# Kasli-DIOT.net
KiCad netlist of a schematic drawn in Altium Designer
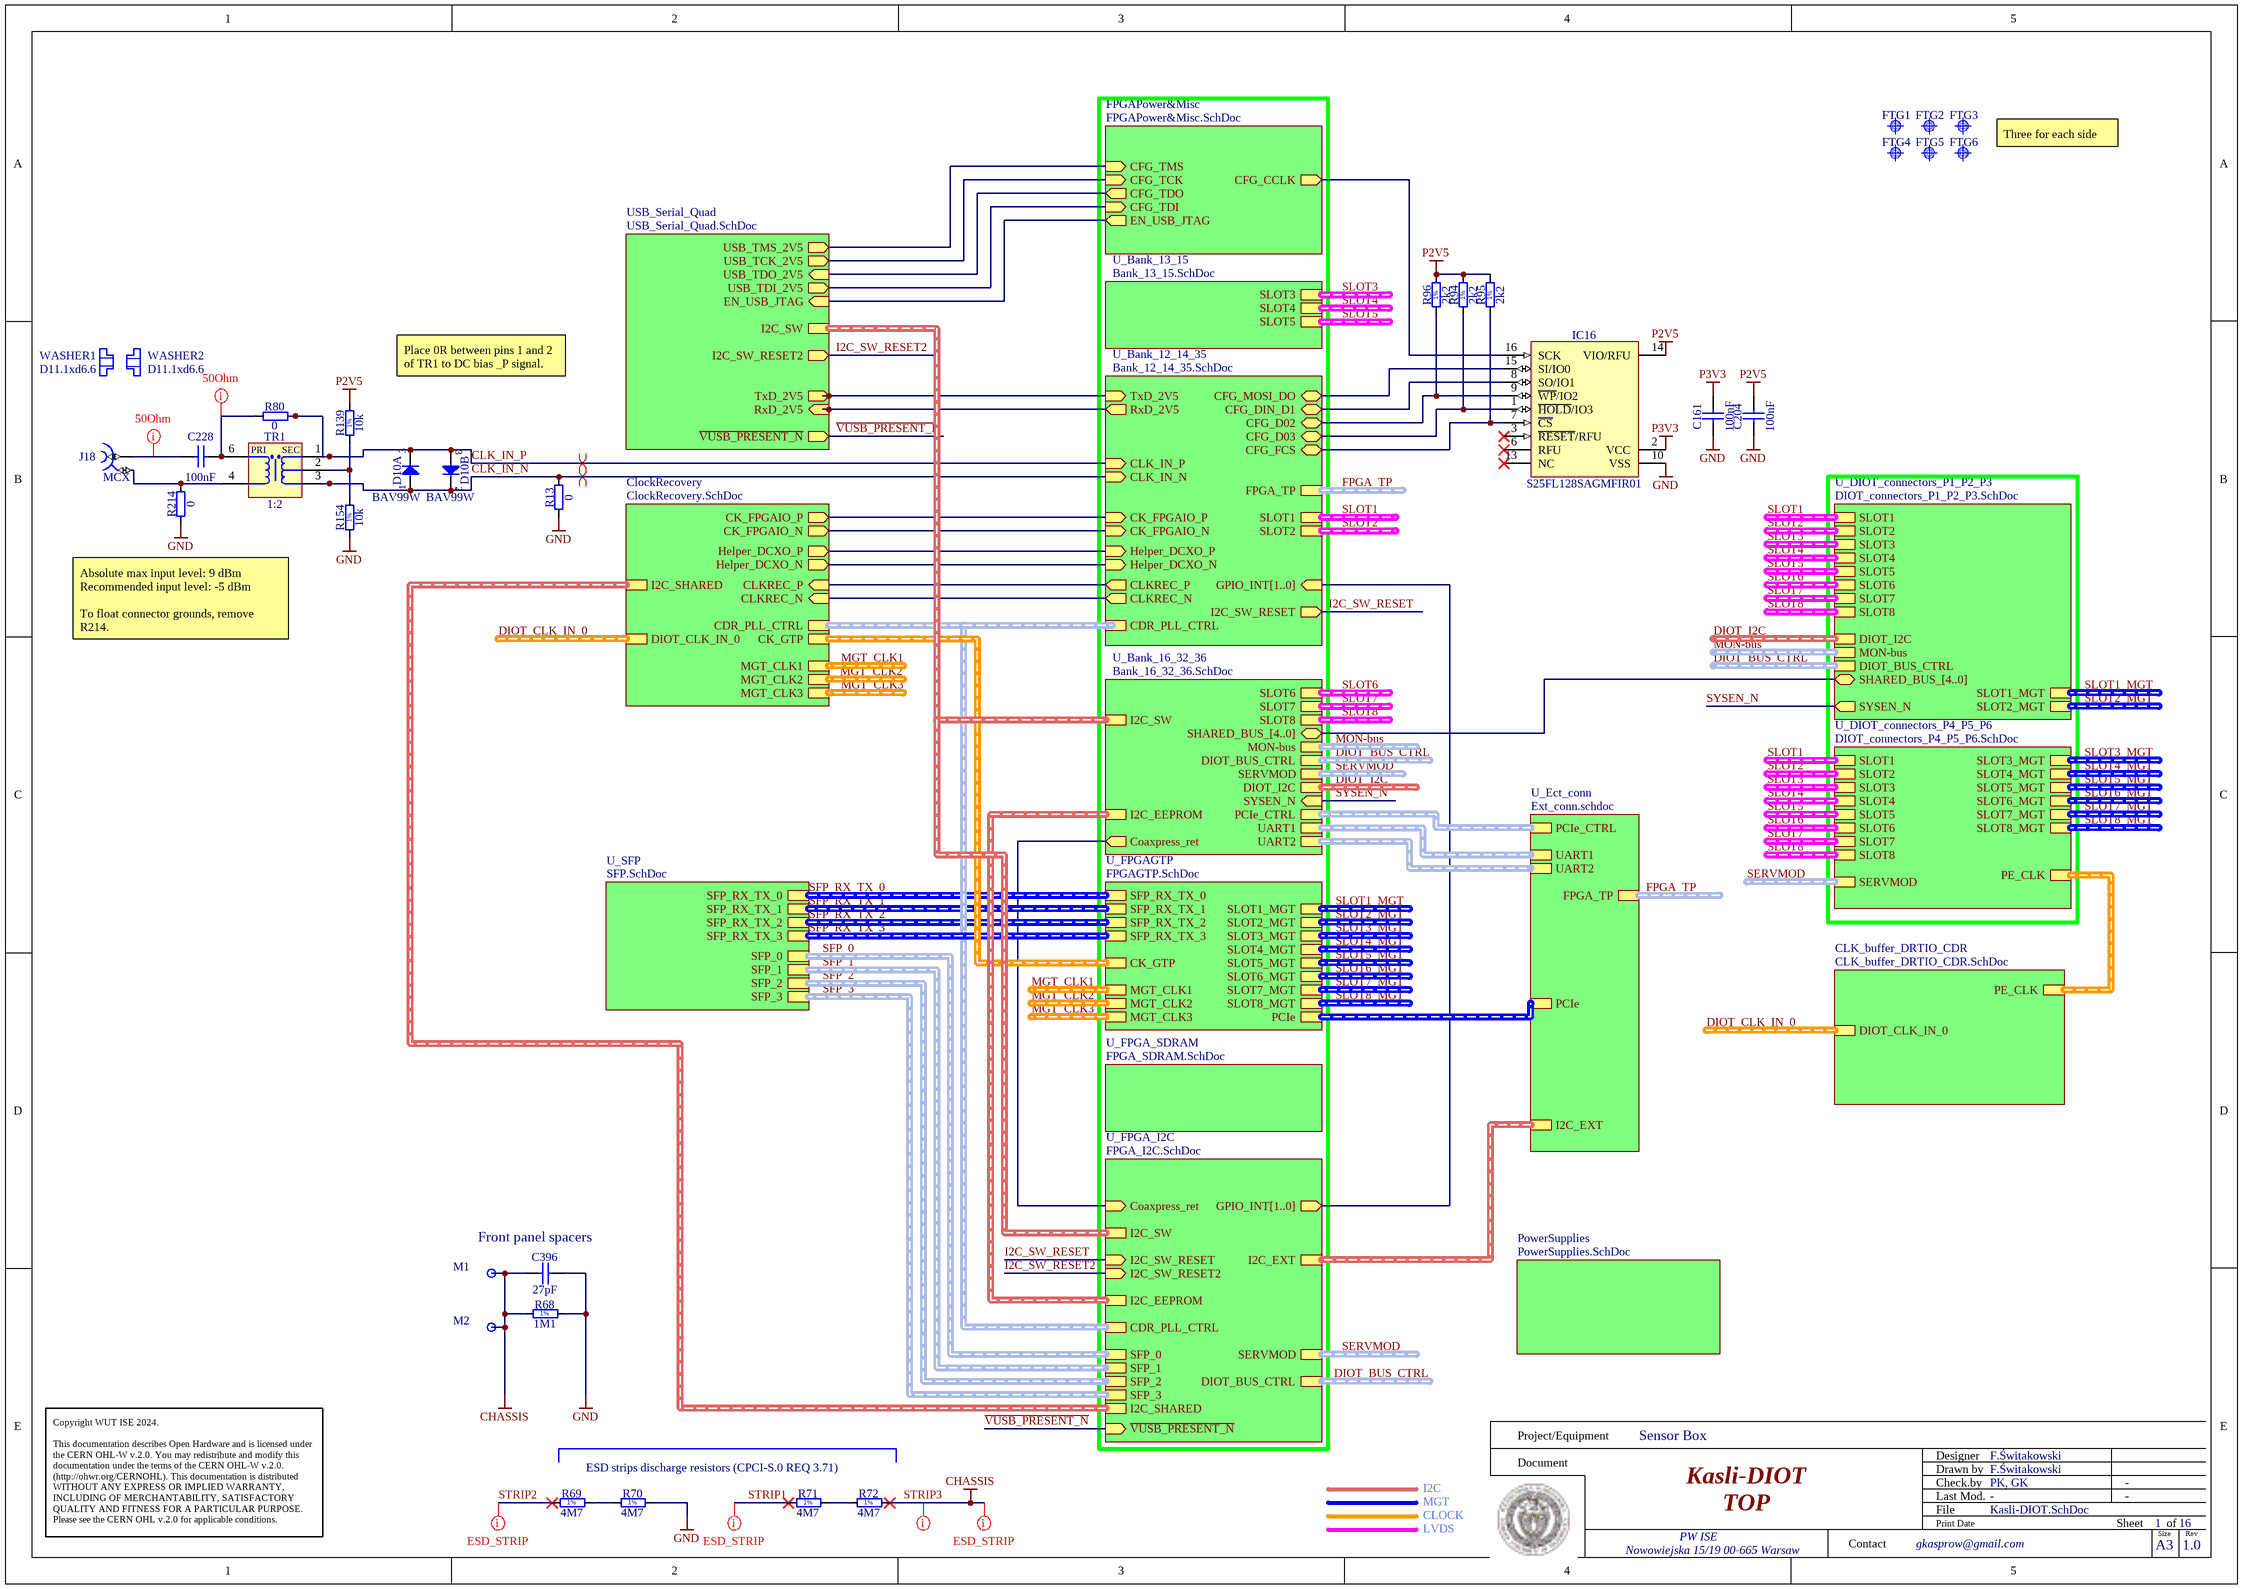
[diagram p0: Kasli-DIOT.SchDoc]

(export (version "E")
  (design (tool "Eeschema 10.0.6"))
  (components
    (comp (ref "C161")
      (value "100nF")
      (footprint "CAPC1005X55N")
      (description "Non-polarised capacitor")
      (fields
        (field (name "PART NUMBER") "CC0402_100NF_16V_10%_X7R")
        (field (name "VOLTAGE") "16V")
        (field (name "AUTHOR") "CERN DEM JLC")
      )
      (libsource (lib "Capacitors") (part "Capacitor - non polarized"))
    )
    (comp (ref "C204")
      (value "100nF")
      (footprint "CAPC1005X55N")
      (description "Non-polarised capacitor")
      (fields
        (field (name "PART NUMBER") "CC0402_100NF_16V_10%_X7R")
        (field (name "VOLTAGE") "16V")
        (field (name "AUTHOR") "CERN DEM JLC")
      )
      (libsource (lib "Capacitors") (part "Capacitor - non polarized"))
    )
    (comp (ref "C228")
      (value "100nF")
      (footprint "CAPC0603X33N")
      (description "Non-polarised capacitor")
      (fields
        (field (name "PART NUMBER") "CC0201_100NF_6.3V_10%_X5R")
        (field (name "VOLTAGE") "6.3V")
        (field (name "AUTHOR") "CERN DEM JLC")
      )
      (libsource (lib "Capacitors") (part "Capacitor - non polarized"))
    )
    (comp (ref "C396")
      (value "27pF")
      (footprint "CAPC1005X55N")
      (description "Non-polarised capacitor")
      (fields
        (field (name "PART NUMBER") "CC0402_27PF_50V_5%_C0G")
        (field (name "VOLTAGE") "50V")
        (field (name "AUTHOR") "CERN DEM JLC")
      )
      (libsource (lib "Capacitors") (part "Capacitor - non polarized"))
    )
    (comp (ref "D10")
      (value "BAV99W")
      (footprint "SOT65P210X110-3N")
      (description "Serial Diode")
      (fields
        (field (name "PART NUMBER") "BAV99W-7-F")
        (field (name "VOLTAGE") "75V")
        (field (name "AUTHOR") "CERN DEM MR")
      )
      (libsource (lib "ICs And Semiconductors") (part "Diode x2 A1C3_A3C2"))
    )
    (comp (ref "FTG1")
      (value "Use only in PCB")
      (footprint "FIDUCIAL_TOP_S100-200")
      (description "Fiducial Target")
      (fields (field (name "PART NUMBER") "FIDUCIAL_TARGET_S100-200") (field (name "AUTHOR") "CERN DEM JLC"))
      (libsource (lib "Eletro-mechanical") (part "Fiducial Target"))
    )
    (comp (ref "FTG2")
      (value "Use only in PCB")
      (footprint "FIDUCIAL_TOP_S100-200")
      (description "Fiducial Target")
      (fields (field (name "PART NUMBER") "FIDUCIAL_TARGET_S100-200") (field (name "AUTHOR") "CERN DEM JLC"))
      (libsource (lib "Eletro-mechanical") (part "Fiducial Target"))
    )
    (comp (ref "FTG3")
      (value "Use only in PCB")
      (footprint "FIDUCIAL_TOP_S100-200")
      (description "Fiducial Target")
      (fields (field (name "PART NUMBER") "FIDUCIAL_TARGET_S100-200") (field (name "AUTHOR") "CERN DEM JLC"))
      (libsource (lib "Eletro-mechanical") (part "Fiducial Target"))
    )
    (comp (ref "FTG4")
      (value "Use only in PCB")
      (footprint "FIDUCIAL_TOP_S100-200")
      (description "Fiducial Target")
      (fields (field (name "PART NUMBER") "FIDUCIAL_TARGET_S100-200") (field (name "AUTHOR") "CERN DEM JLC"))
      (libsource (lib "Eletro-mechanical") (part "Fiducial Target"))
    )
    (comp (ref "FTG5")
      (value "Use only in PCB")
      (footprint "FIDUCIAL_TOP_S100-200")
      (description "Fiducial Target")
      (fields (field (name "PART NUMBER") "FIDUCIAL_TARGET_S100-200") (field (name "AUTHOR") "CERN DEM JLC"))
      (libsource (lib "Eletro-mechanical") (part "Fiducial Target"))
    )
    (comp (ref "FTG6")
      (value "Use only in PCB")
      (footprint "FIDUCIAL_TOP_S100-200")
      (description "Fiducial Target")
      (fields (field (name "PART NUMBER") "FIDUCIAL_TARGET_S100-200") (field (name "AUTHOR") "CERN DEM JLC"))
      (libsource (lib "Eletro-mechanical") (part "Fiducial Target"))
    )
    (comp (ref "IC16")
      (value "S25FL128SAGMFIR01")
      (footprint "SOIC127P1030X265-16N")
      (fields (field (name "MANUFACTURER") "SPANSION") (field (name "AUTHOR") "CERN DEM JLC"))
      (libsource (lib "ICs And Semiconductors") (part "S25FL128SAGMFIR01"))
    )
    (comp (ref "J18")
      (value "MCX")
      (footprint "AMPHENOL_919-383J-51A")
      (fields
        (field (name "PART NUMBER") "AMPHENOL_919-383J-51A")
        (field (name "MANUFACTURER") "AMPHENOL")
        (field (name "MANUFACTURER PART NUMBER") "919-383J-51A")
        (field (name "AUTHOR") "CERN DEM BC")
      )
      (libsource (lib "Connectors") (part "Coax_1Female_1Shield"))
    )
    (comp (ref "M1")
      (value "Plated Hole")
      (footprint "MTG300_600")
      (description "Single Terminal Socket")
      (fields (field (name "PART NUMBER") "PLATED_HOLE3.0_PAD6.0") (field (name "AUTHOR") "CERN DEM JLC"))
      (libsource (lib "Eletro-mechanical") (part "Single Terminal Socket"))
    )
    (comp (ref "M2")
      (value "Plated Hole")
      (footprint "MTG300_600")
      (description "Single Terminal Socket")
      (fields (field (name "PART NUMBER") "PLATED_HOLE3.0_PAD6.0") (field (name "AUTHOR") "CERN DEM JLC"))
      (libsource (lib "Eletro-mechanical") (part "Single Terminal Socket"))
    )
    (comp (ref "R13")
      (value "0")
      (footprint "RESC1005X40N")
      (description "Resistor")
      (fields
        (field (name "PART NUMBER") "R0402_0R_JUMPER")
        (field (name "MANUFACTURER") "GENERIC")
        (field (name "AUTHOR") "CERN DEM JLC")
      )
      (libsource (lib "Resistors") (part "Resistor"))
    )
    (comp (ref "R68")
      (value "1M1")
      (footprint "RESC2012X60N")
      (description "Resistor - 1%")
      (fields
        (field (name "PART NUMBER") "R0805_1M1_1%_0.125W_100PPM")
        (field (name "POWER") "0.125W")
        (field (name "AUTHOR") "CERN DEM JLC")
      )
      (libsource (lib "Resistors") (part "Resistor - 1%"))
    )
    (comp (ref "R69")
      (value "4M7")
      (footprint "RESC2113X55N")
      (description "Resistor - 1%")
      (fields
        (field (name "PART NUMBER") "R0805_4M7_1%_0.125W_100PPM_VISHAY_CRCW e3")
        (field (name "POWER") "0.125W")
        (field (name "AUTHOR") "CERN DEM BR")
      )
      (libsource (lib "Resistors") (part "Resistor - 1%"))
    )
    (comp (ref "R70")
      (value "4M7")
      (footprint "RESC2113X55N")
      (description "Resistor - 1%")
      (fields
        (field (name "PART NUMBER") "R0805_4M7_1%_0.125W_100PPM_VISHAY_CRCW e3")
        (field (name "POWER") "0.125W")
        (field (name "AUTHOR") "CERN DEM BR")
      )
      (libsource (lib "Resistors") (part "Resistor - 1%"))
    )
    (comp (ref "R71")
      (value "4M7")
      (footprint "RESC2113X55N")
      (description "Resistor - 1%")
      (fields
        (field (name "PART NUMBER") "R0805_4M7_1%_0.125W_100PPM_VISHAY_CRCW e3")
        (field (name "POWER") "0.125W")
        (field (name "AUTHOR") "CERN DEM BR")
      )
      (libsource (lib "Resistors") (part "Resistor - 1%"))
    )
    (comp (ref "R72")
      (value "4M7")
      (footprint "RESC2113X55N")
      (description "Resistor - 1%")
      (fields
        (field (name "PART NUMBER") "R0805_4M7_1%_0.125W_100PPM_VISHAY_CRCW e3")
        (field (name "POWER") "0.125W")
        (field (name "AUTHOR") "CERN DEM BR")
      )
      (libsource (lib "Resistors") (part "Resistor - 1%"))
    )
    (comp (ref "R80")
      (value "0")
      (footprint "RESC1005X40N")
      (description "Resistor")
      (fields
        (field (name "PART NUMBER") "R0402_0R_JUMPER")
        (field (name "MANUFACTURER") "GENERIC")
        (field (name "AUTHOR") "CERN DEM JLC")
      )
      (libsource (lib "Resistors") (part "Resistor"))
    )
    (comp (ref "R94")
      (value "2k2")
      (footprint "RESC1005X40N")
      (description "Resistor - 1%")
      (fields
        (field (name "PART NUMBER") "R0402_2K2_1%_0.0625W_100PPM")
        (field (name "POWER") "0.0625W")
        (field (name "AUTHOR") "CERN DEM JLC")
      )
      (libsource (lib "Resistors") (part "Resistor - 1%"))
    )
    (comp (ref "R95")
      (value "2k2")
      (footprint "RESC1005X40N")
      (description "Resistor - 1%")
      (fields
        (field (name "PART NUMBER") "R0402_2K2_1%_0.0625W_100PPM")
        (field (name "POWER") "0.0625W")
        (field (name "AUTHOR") "CERN DEM JLC")
      )
      (libsource (lib "Resistors") (part "Resistor - 1%"))
    )
    (comp (ref "R96")
      (value "2k2")
      (footprint "RESC1005X40N")
      (description "Resistor - 1%")
      (fields
        (field (name "PART NUMBER") "R0402_2K2_1%_0.0625W_100PPM")
        (field (name "POWER") "0.0625W")
        (field (name "AUTHOR") "CERN DEM JLC")
      )
      (libsource (lib "Resistors") (part "Resistor - 1%"))
    )
    (comp (ref "R139")
      (value "10k")
      (footprint "RESC1005X40N")
      (description "Resistor - 1%")
      (fields
        (field (name "PART NUMBER") "R0402_10K_1%_0.0625W_100PPM")
        (field (name "POWER") "0.0625W")
        (field (name "AUTHOR") "CERN DEM JLC")
      )
      (libsource (lib "Resistors") (part "Resistor - 1%"))
    )
    (comp (ref "R154")
      (value "10k")
      (footprint "RESC1005X40N")
      (description "Resistor - 1%")
      (fields
        (field (name "PART NUMBER") "R0402_10K_1%_0.0625W_100PPM")
        (field (name "POWER") "0.0625W")
        (field (name "AUTHOR") "CERN DEM JLC")
      )
      (libsource (lib "Resistors") (part "Resistor - 1%"))
    )
    (comp (ref "R214")
      (value "0")
      (footprint "RESC1005X40N")
      (description "Resistor")
      (fields
        (field (name "PART NUMBER") "R0402_0R_JUMPER")
        (field (name "MANUFACTURER") "GENERIC")
        (field (name "AUTHOR") "CERN DEM JLC")
      )
      (libsource (lib "Resistors") (part "Resistor"))
    )
    (comp (ref "TR1")
      (value "1:2")
      (footprint "XFMR_MINI-CIRCUITS_AT1521")
      (description "50 Ohms 3 to 300MHz RF Transformer")
      (fields
        (field (name "PART NUMBER") "XFMR_MINI-CIRCUITS_TC2-1TX+")
        (field (name "MANUFACTURER") "MINI-CIRCUITS")
        (field (name "AUTHOR") "CERN DEM MR")
      )
      (libsource (lib "Inductors & Transformers") (part "XFMR_MINI-CIRCUITS_TC2-1TX+"))
    )
    (comp (ref "WASHER1")
      (value "D11.1xd6.6")
      (footprint "Keystone_7687")
      (description "SMA_Shoulder Washer")
      (fields
        (field (name "PART NUMBER") "Keystone 7687")
        (field (name "MANUFACTURER") "Keystone")
        (field (name "AUTHOR") "GK")
      )
      (libsource (lib "LIBRARY_SCH") (part "Keystone_7687"))
    )
    (comp (ref "WASHER2")
      (value "D11.1xd6.6")
      (footprint "Keystone_7687")
      (description "SMA_Shoulder Washer")
      (fields
        (field (name "PART NUMBER") "Keystone 7687")
        (field (name "MANUFACTURER") "Keystone")
        (field (name "AUTHOR") "GK")
      )
      (libsource (lib "LIBRARY_SCH") (part "Keystone_7687"))
    )
  )
  (nets
    (net (code "35") (name "/CFG_CCLK") (class "Default")
      (node (ref "IC16") (pin "16") (pinfunction "SCK_16") (pintype "input"))
    )
    (net (code "36") (name "/CFG_D02") (class "Default")
      (node (ref "IC16") (pin "9") (pinfunction "~{WP}/IO2_9") (pintype "bidirectional"))
      (node (ref "R96") (pin "1") (pinfunction "1_1") (pintype "passive"))
    )
    (net (code "37") (name "/CFG_D03") (class "Default")
      (node (ref "IC16") (pin "1") (pinfunction "~{HOLD}/IO3_1") (pintype "bidirectional"))
      (node (ref "R94") (pin "1") (pinfunction "1_1") (pintype "passive"))
    )
    (net (code "38") (name "/CFG_DIN_D1") (class "Default")
      (node (ref "IC16") (pin "8") (pinfunction "SO/IO1_8") (pintype "bidirectional"))
    )
    (net (code "39") (name "/CFG_FCS") (class "Default")
      (node (ref "IC16") (pin "7") (pinfunction "~{CS}_7") (pintype "input"))
      (node (ref "R95") (pin "1") (pinfunction "1_1") (pintype "passive"))
    )
    (net (code "40") (name "/CFG_MOSI_DO") (class "Default")
      (node (ref "IC16") (pin "15") (pinfunction "SI/IO0_15") (pintype "bidirectional"))
    )
    (net (code "47") (name "/CLK_IN_N") (class "Default")
      (node (ref "D10") (pin "1") (pinfunction "A_1") (pintype "passive"))
      (node (ref "D10") (pin "2") (pinfunction "C_2") (pintype "passive"))
      (node (ref "R13") (pin "2") (pinfunction "2_2") (pintype "passive"))
      (node (ref "TR1") (pin "3") (pinfunction "S_3") (pintype "passive"))
    )
    (net (code "48") (name "/CLK_IN_P") (class "Default")
      (node (ref "D10") (pin "3") (pinfunction "COMAC_3") (pintype "passive"))
      (node (ref "R80") (pin "2") (pinfunction "2_2") (pintype "passive"))
      (node (ref "TR1") (pin "1") (pinfunction "SDOT_1") (pintype "passive"))
    )
    (net (code "65") (name "/STRIP1") (class "Default")
      (node (ref "R71") (pin "1") (pinfunction "1_1") (pintype "passive+no_connect"))
    )
    (net (code "66") (name "/STRIP2") (class "Default")
      (node (ref "R69") (pin "1") (pinfunction "1_1") (pintype "passive+no_connect"))
    )
    (net (code "108") (name "CHASSIS") (class "Default")
      (node (ref "C396") (pin "1") (pinfunction "1_1") (pintype "passive"))
      (node (ref "M1") (pin "1") (pinfunction "1_1") (pintype "bidirectional"))
      (node (ref "M2") (pin "1") (pinfunction "1_1") (pintype "bidirectional"))
      (node (ref "R68") (pin "1") (pinfunction "1_1") (pintype "passive"))
      (node (ref "R72") (pin "2") (pinfunction "2_2") (pintype "passive"))
    )
    (net (code "109") (name "GND") (class "Default")
      (node (ref "C161") (pin "1") (pinfunction "1_1") (pintype "passive"))
      (node (ref "C204") (pin "1") (pinfunction "1_1") (pintype "passive"))
      (node (ref "C396") (pin "2") (pinfunction "2_2") (pintype "passive"))
      (node (ref "IC16") (pin "10") (pinfunction "VSS_10") (pintype "power_in"))
      (node (ref "R13") (pin "1") (pinfunction "1_1") (pintype "passive"))
      (node (ref "R154") (pin "2") (pinfunction "2_2") (pintype "passive"))
      (node (ref "R214") (pin "1") (pinfunction "1_1") (pintype "passive"))
      (node (ref "R68") (pin "2") (pinfunction "2_2") (pintype "passive"))
      (node (ref "R70") (pin "2") (pinfunction "2_2") (pintype "passive"))
    )
    (net (code "110") (name "Net-(C228-Pad1)") (class "Default")
      (node (ref "C228") (pin "1") (pinfunction "1_1") (pintype "passive"))
      (node (ref "J18") (pin "1") (pinfunction "1_1") (pintype "bidirectional"))
    )
    (net (code "111") (name "Net-(R69-Pad2)") (class "Default")
      (node (ref "R69") (pin "2") (pinfunction "2_2") (pintype "passive"))
      (node (ref "R70") (pin "1") (pinfunction "1_1") (pintype "passive"))
    )
    (net (code "112") (name "Net-(R71-Pad2)") (class "Default")
      (node (ref "R71") (pin "2") (pinfunction "2_2") (pintype "passive"))
      (node (ref "R72") (pin "1") (pinfunction "1_1") (pintype "passive"))
    )
    (net (code "113") (name "Net-(TR1-NC)") (class "Default")
      (node (ref "R139") (pin "2") (pinfunction "2_2") (pintype "passive"))
      (node (ref "R154") (pin "1") (pinfunction "1_1") (pintype "passive"))
      (node (ref "TR1") (pin "2") (pinfunction "NC_2") (pintype "passive"))
    )
    (net (code "114") (name "Net-(TR1-P)") (class "Default")
      (node (ref "J18") (pin "2") (pinfunction "2_2") (pintype "bidirectional"))
      (node (ref "R214") (pin "2") (pinfunction "2_2") (pintype "passive"))
      (node (ref "TR1") (pin "4") (pinfunction "P_4") (pintype "passive"))
    )
    (net (code "115") (name "Net-(TR1-PDOT)") (class "Default")
      (node (ref "C228") (pin "2") (pinfunction "2_2") (pintype "passive"))
      (node (ref "R80") (pin "1") (pinfunction "1_1") (pintype "passive"))
      (node (ref "TR1") (pin "6") (pinfunction "PDOT_6") (pintype "passive"))
    )
    (net (code "116") (name "P2V5") (class "Default")
      (node (ref "C204") (pin "2") (pinfunction "2_2") (pintype "passive"))
      (node (ref "IC16") (pin "14") (pinfunction "VIO/RFU_14") (pintype "power_in"))
      (node (ref "R139") (pin "1") (pinfunction "1_1") (pintype "passive"))
      (node (ref "R94") (pin "2") (pinfunction "2_2") (pintype "passive"))
      (node (ref "R95") (pin "2") (pinfunction "2_2") (pintype "passive"))
      (node (ref "R96") (pin "2") (pinfunction "2_2") (pintype "passive"))
    )
    (net (code "117") (name "P3V3") (class "Default")
      (node (ref "C161") (pin "2") (pinfunction "2_2") (pintype "passive"))
      (node (ref "IC16") (pin "2") (pinfunction "VCC_2") (pintype "power_in"))
    )
    (net (code "118") (name "unconnected-(IC16-NC-Pad13)") (class "Default")
      (node (ref "IC16") (pin "13") (pinfunction "NC_13") (pintype "passive+no_connect"))
    )
    (net (code "119") (name "unconnected-(IC16-RFU-Pad6)") (class "Default")
      (node (ref "IC16") (pin "6") (pinfunction "RFU_6") (pintype "passive+no_connect"))
    )
    (net (code "120") (name "unconnected-(IC16-~{RESET}{slash}RFU-Pad3)") (class "Default")
      (node (ref "IC16") (pin "3") (pinfunction "~{RESET}/RFU_3") (pintype "input+no_connect"))
    )
  )
)
